# PCB.net
KiCad netlist of a schematic drawn in EAGLE
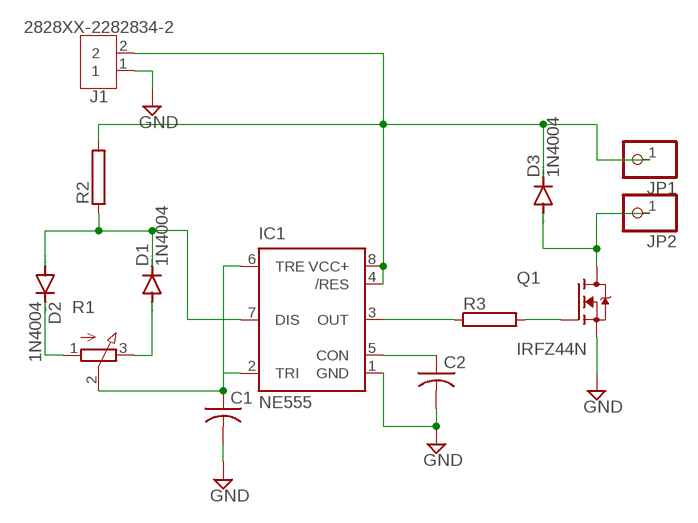
[diagram p0: schematic, sheet 1]

(export (version "E")
  (design (tool "Eeschema 10.0.6"))
  (components
    (comp (ref "C1")
      (value "C-US025-024X044")
      (footprint "eagle-import:C025-024X044")
      (libsource (lib "eagle-import") (part "C-US025-024X044"))
    )
    (comp (ref "C2")
      (value "C-US025-024X044")
      (footprint "eagle-import:C025-024X044")
      (libsource (lib "eagle-import") (part "C-US025-024X044"))
    )
    (comp (ref "D1")
      (value "1N4004")
      (footprint "eagle-import:DO41-10")
      (libsource (lib "eagle-import") (part "1N4004"))
    )
    (comp (ref "D2")
      (value "1N4004")
      (footprint "eagle-import:DO41-10")
      (libsource (lib "eagle-import") (part "1N4004"))
    )
    (comp (ref "D3")
      (value "1N4004")
      (footprint "eagle-import:DO41-10")
      (libsource (lib "eagle-import") (part "1N4004"))
    )
    (comp (ref "IC1")
      (value "NE555")
      (footprint "eagle-import:DIL-08")
      (fields (field (name "MF") "Arrow Electronics") (field (name "MPN") "NE555N"))
      (libsource (lib "eagle-import") (part "NE555"))
    )
    (comp (ref "J1")
      (value "2828XX-2282834-2")
      (footprint "eagle-import:TERMBLK_254-2N")
      (fields (field (name "MANUFACTURER") "TE Connectivity AMP Connectors") (field (name "MPN") "282834-2 "))
      (libsource (lib "eagle-import") (part "2828XX-2282834-2"))
    )
    (comp (ref "JP1")
      (value "PINHD-1X1")
      (footprint "eagle-import:1X01")
      (libsource (lib "eagle-import") (part "PINHD-1X1"))
    )
    (comp (ref "JP2")
      (value "PINHD-1X1")
      (footprint "eagle-import:1X01")
      (libsource (lib "eagle-import") (part "PINHD-1X1"))
    )
    (comp (ref "Q1")
      (value "IRFZ44N")
      (footprint "eagle-import:TO254P1016X419X2286-3")
      (fields (field (name "MF") "Infineon Technologies"))
      (libsource (lib "eagle-import") (part "IRFZ44N"))
    )
    (comp (ref "R1")
      (value "3RP/1610N")
      (footprint "eagle-import:3RP_1610N")
      (libsource (lib "eagle-import") (part "3RP/1610N"))
    )
    (comp (ref "R2")
      (value "RAC01")
      (footprint "eagle-import:AC01")
      (libsource (lib "eagle-import") (part "RAC01"))
    )
    (comp (ref "R3")
      (value "RAC01")
      (footprint "eagle-import:AC01")
      (libsource (lib "eagle-import") (part "RAC01"))
    )
  )
  (nets
    (net (code "1") (name "GND") (class "Default")
      (node (ref "C1") (pin "2") (pinfunction "2_2") (pintype "passive"))
      (node (ref "C2") (pin "2") (pinfunction "2_2") (pintype "passive"))
      (node (ref "IC1") (pin "1") (pinfunction "GND_1") (pintype "power_in"))
      (node (ref "J1") (pin "1") (pinfunction "1_1") (pintype "bidirectional"))
      (node (ref "Q1") (pin "3") (pinfunction "S_3") (pintype "passive"))
    )
    (net (code "2") (name "Net-(IC1-CON)") (class "Default")
      (node (ref "C2") (pin "1") (pinfunction "1_1") (pintype "passive"))
      (node (ref "IC1") (pin "5") (pinfunction "CON_5") (pintype "input"))
    )
    (net (code "3") (name "Net-(IC1-DIS)") (class "Default")
      (node (ref "D1") (pin "C") (pinfunction "C_C") (pintype "passive"))
      (node (ref "D2") (pin "A") (pinfunction "A_A") (pintype "passive"))
      (node (ref "IC1") (pin "7") (pinfunction "DIS_7") (pintype "input"))
      (node (ref "R2") (pin "1") (pinfunction "1_1") (pintype "passive"))
    )
    (net (code "4") (name "Net-(IC1-OUT)") (class "Default")
      (node (ref "IC1") (pin "3") (pinfunction "OUT_3") (pintype "output"))
      (node (ref "R3") (pin "1") (pinfunction "1_1") (pintype "passive"))
    )
    (net (code "5") (name "Net-(IC1-TRE)") (class "Default")
      (node (ref "C1") (pin "1") (pinfunction "1_1") (pintype "passive"))
      (node (ref "IC1") (pin "2") (pinfunction "TRI_2") (pintype "input"))
      (node (ref "IC1") (pin "6") (pinfunction "TRE_6") (pintype "input"))
      (node (ref "R1") (pin "2") (pinfunction "S_2") (pintype "passive"))
    )
    (net (code "6") (name "Net-(IC1-VCC+)") (class "Default")
      (node (ref "D3") (pin "C") (pinfunction "C_C") (pintype "passive"))
      (node (ref "IC1") (pin "4") (pinfunction "/RES_4") (pintype "input"))
      (node (ref "IC1") (pin "8") (pinfunction "VCC+_8") (pintype "power_in"))
      (node (ref "J1") (pin "2") (pinfunction "2_2") (pintype "bidirectional"))
      (node (ref "JP1") (pin "1") (pinfunction "1_1") (pintype "passive"))
      (node (ref "R2") (pin "2") (pinfunction "2_2") (pintype "passive"))
    )
    (net (code "7") (name "Net-(Q1-D)") (class "Default")
      (node (ref "D3") (pin "A") (pinfunction "A_A") (pintype "passive"))
      (node (ref "JP2") (pin "1") (pinfunction "1_1") (pintype "passive"))
      (node (ref "Q1") (pin "2") (pinfunction "D_2") (pintype "passive"))
    )
    (net (code "8") (name "Net-(Q1-G)") (class "Default")
      (node (ref "Q1") (pin "1") (pinfunction "G_1") (pintype "passive"))
      (node (ref "R3") (pin "2") (pinfunction "2_2") (pintype "passive"))
    )
    (net (code "9") (name "Net-(R1-A)") (class "Default")
      (node (ref "D2") (pin "C") (pinfunction "C_C") (pintype "passive"))
      (node (ref "R1") (pin "1") (pinfunction "A_1") (pintype "passive"))
    )
    (net (code "10") (name "Net-(R1-E)") (class "Default")
      (node (ref "D1") (pin "A") (pinfunction "A_A") (pintype "passive"))
      (node (ref "R1") (pin "3") (pinfunction "E_3") (pintype "passive"))
    )
  )
)
